# motorboard.net
KiCad netlist of a schematic drawn in EAGLE
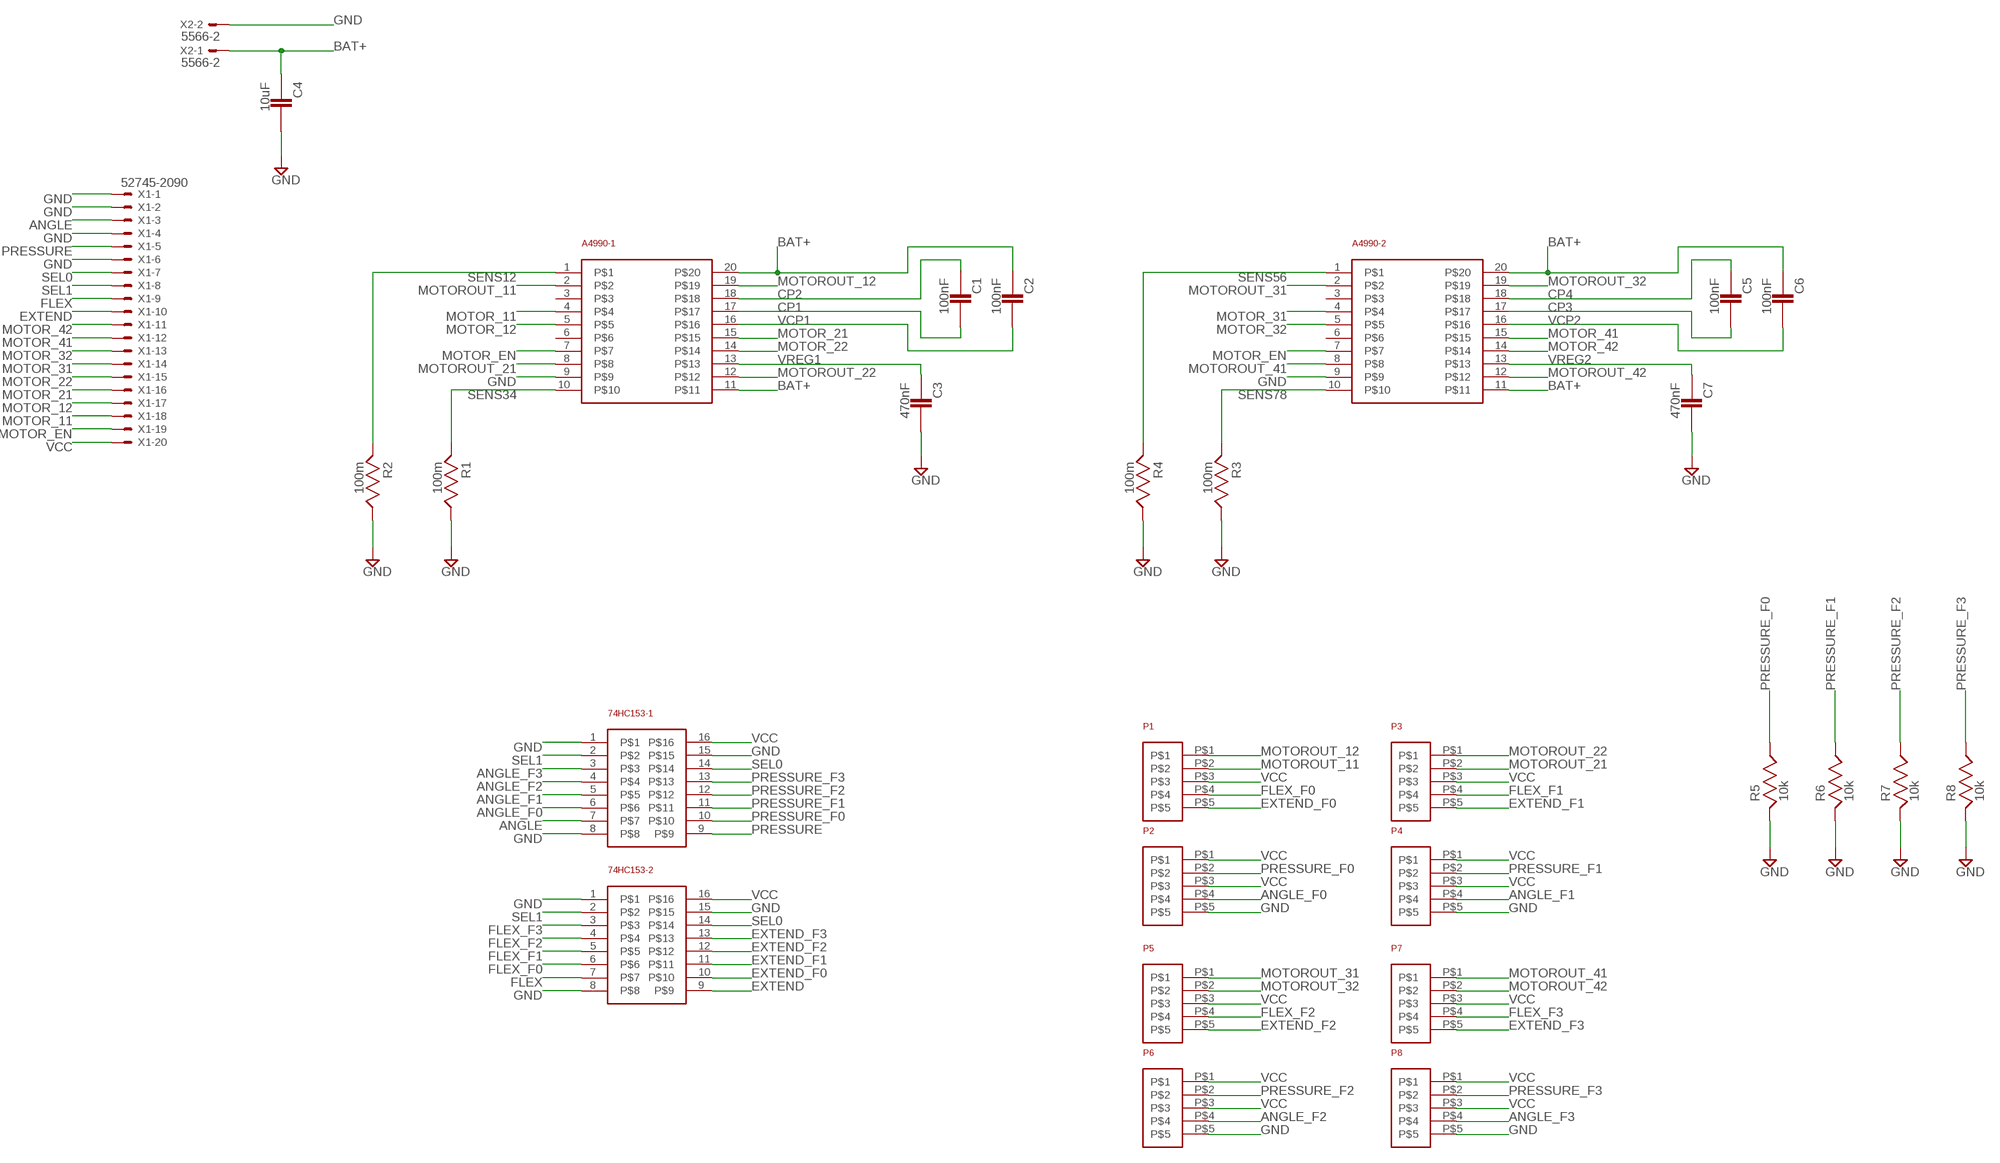
[diagram p0: schematic, sheet 1]

(export (version "E")
  (design (tool "Eeschema 10.0.6"))
  (components
    (comp (ref "74HC153-1")
      (value "74HC153")
      (footprint "eagle-import:SO-16_S-M")
      (libsource (lib "eagle-import") (part "74HC153"))
    )
    (comp (ref "74HC153-2")
      (value "74HC153")
      (footprint "eagle-import:SO-16_S-M")
      (libsource (lib "eagle-import") (part "74HC153"))
    )
    (comp (ref "A4990-1")
      (value "A4990")
      (footprint "eagle-import:A4990")
      (libsource (lib "eagle-import") (part "A4990"))
    )
    (comp (ref "A4990-2")
      (value "A4990")
      (footprint "eagle-import:A4990")
      (libsource (lib "eagle-import") (part "A4990"))
    )
    (comp (ref "C1")
      (value "100nF")
      (footprint "eagle-import:CC0603KRX7R9BB104_CAPC1608X90")
      (fields (field (name "MANUFACTURER") "YAGEO"))
      (libsource (lib "eagle-import") (part "CC0603KRX7R9BB104"))
    )
    (comp (ref "C2")
      (value "100nF")
      (footprint "eagle-import:CC0603KRX7R9BB104_CAPC1608X90")
      (fields (field (name "MANUFACTURER") "YAGEO"))
      (libsource (lib "eagle-import") (part "CC0603KRX7R9BB104"))
    )
    (comp (ref "C3")
      (value "470nF")
      (footprint "eagle-import:CC0603KRX7R9BB104_CAPC1608X90")
      (fields (field (name "MANUFACTURER") "YAGEO"))
      (libsource (lib "eagle-import") (part "CC0603KRX7R9BB104"))
    )
    (comp (ref "C4")
      (value "10uF")
      (footprint "eagle-import:CC0603KRX7R9BB104_CAPC1608X90")
      (fields (field (name "MANUFACTURER") "YAGEO"))
      (libsource (lib "eagle-import") (part "CC0603KRX7R9BB104"))
    )
    (comp (ref "C5")
      (value "100nF")
      (footprint "eagle-import:CC0603KRX7R9BB104_CAPC1608X90")
      (fields (field (name "MANUFACTURER") "YAGEO"))
      (libsource (lib "eagle-import") (part "CC0603KRX7R9BB104"))
    )
    (comp (ref "C6")
      (value "100nF")
      (footprint "eagle-import:CC0603KRX7R9BB104_CAPC1608X90")
      (fields (field (name "MANUFACTURER") "YAGEO"))
      (libsource (lib "eagle-import") (part "CC0603KRX7R9BB104"))
    )
    (comp (ref "C7")
      (value "470nF")
      (footprint "eagle-import:CC0603KRX7R9BB104_CAPC1608X90")
      (fields (field (name "MANUFACTURER") "YAGEO"))
      (libsource (lib "eagle-import") (part "CC0603KRX7R9BB104"))
    )
    (comp (ref "P1")
      (value "S5B-PH-SM4-TB")
      (footprint "eagle-import:S5B-PH-SM4-TB")
      (libsource (lib "eagle-import") (part "S5B-PH-SM4-TB"))
    )
    (comp (ref "P2")
      (value "S5B-PH-SM4-TB")
      (footprint "eagle-import:S5B-PH-SM4-TB")
      (libsource (lib "eagle-import") (part "S5B-PH-SM4-TB"))
    )
    (comp (ref "P3")
      (value "S5B-PH-SM4-TB")
      (footprint "eagle-import:S5B-PH-SM4-TB")
      (libsource (lib "eagle-import") (part "S5B-PH-SM4-TB"))
    )
    (comp (ref "P4")
      (value "S5B-PH-SM4-TB")
      (footprint "eagle-import:S5B-PH-SM4-TB")
      (libsource (lib "eagle-import") (part "S5B-PH-SM4-TB"))
    )
    (comp (ref "P5")
      (value "S5B-PH-SM4-TB")
      (footprint "eagle-import:S5B-PH-SM4-TB")
      (libsource (lib "eagle-import") (part "S5B-PH-SM4-TB"))
    )
    (comp (ref "P6")
      (value "S5B-PH-SM4-TB")
      (footprint "eagle-import:S5B-PH-SM4-TB")
      (libsource (lib "eagle-import") (part "S5B-PH-SM4-TB"))
    )
    (comp (ref "P7")
      (value "S5B-PH-SM4-TB")
      (footprint "eagle-import:S5B-PH-SM4-TB")
      (libsource (lib "eagle-import") (part "S5B-PH-SM4-TB"))
    )
    (comp (ref "P8")
      (value "S5B-PH-SM4-TB")
      (footprint "eagle-import:S5B-PH-SM4-TB")
      (libsource (lib "eagle-import") (part "S5B-PH-SM4-TB"))
    )
    (comp (ref "R1")
      (value "100m")
      (footprint "eagle-import:CRCW06031K00FKEA_RESC1608X55")
      (fields (field (name "MANUFACTURER") "VISHAY"))
      (libsource (lib "eagle-import") (part "CRCW06031K00FKEA"))
    )
    (comp (ref "R2")
      (value "100m")
      (footprint "eagle-import:CRCW06031K00FKEA_RESC1608X55")
      (fields (field (name "MANUFACTURER") "VISHAY"))
      (libsource (lib "eagle-import") (part "CRCW06031K00FKEA"))
    )
    (comp (ref "R3")
      (value "100m")
      (footprint "eagle-import:CRCW06031K00FKEA_RESC1608X55")
      (fields (field (name "MANUFACTURER") "VISHAY"))
      (libsource (lib "eagle-import") (part "CRCW06031K00FKEA"))
    )
    (comp (ref "R4")
      (value "100m")
      (footprint "eagle-import:CRCW06031K00FKEA_RESC1608X55")
      (fields (field (name "MANUFACTURER") "VISHAY"))
      (libsource (lib "eagle-import") (part "CRCW06031K00FKEA"))
    )
    (comp (ref "R5")
      (value "10k")
      (footprint "eagle-import:CRCW06031K00FKEA_RESC1608X55")
      (fields (field (name "MANUFACTURER") "VISHAY"))
      (libsource (lib "eagle-import") (part "CRCW06031K00FKEA"))
    )
    (comp (ref "R6")
      (value "10k")
      (footprint "eagle-import:CRCW06031K00FKEA_RESC1608X55")
      (fields (field (name "MANUFACTURER") "VISHAY"))
      (libsource (lib "eagle-import") (part "CRCW06031K00FKEA"))
    )
    (comp (ref "R7")
      (value "10k")
      (footprint "eagle-import:CRCW06031K00FKEA_RESC1608X55")
      (fields (field (name "MANUFACTURER") "VISHAY"))
      (libsource (lib "eagle-import") (part "CRCW06031K00FKEA"))
    )
    (comp (ref "R8")
      (value "10k")
      (footprint "eagle-import:CRCW06031K00FKEA_RESC1608X55")
      (fields (field (name "MANUFACTURER") "VISHAY"))
      (libsource (lib "eagle-import") (part "CRCW06031K00FKEA"))
    )
    (comp (ref "X1")
      (value "52745-2090")
      (footprint "eagle-import:52745-2090")
      (fields (field (name "MF") "WALDOM/MOLEX"))
      (libsource (lib "eagle-import") (part "52745-2090"))
    )
    (comp (ref "X2")
      (value "5566-2")
      (footprint "eagle-import:5566-2")
      (libsource (lib "eagle-import") (part "5566-2"))
    )
  )
  (nets
    (net (code "1") (name "/ANGLE") (class "Default")
      (node (ref "74HC153-1") (pin "7") (pinfunction "P$7_7") (pintype "bidirectional"))
      (node (ref "X1") (pin "3") (pinfunction "S_3") (pintype "passive"))
    )
    (net (code "2") (name "/ANGLE_F0") (class "Default")
      (node (ref "74HC153-1") (pin "6") (pinfunction "P$6_6") (pintype "bidirectional"))
      (node (ref "P2") (pin "P$4") (pinfunction "P$4_P$4") (pintype "bidirectional"))
    )
    (net (code "3") (name "/ANGLE_F1") (class "Default")
      (node (ref "74HC153-1") (pin "5") (pinfunction "P$5_5") (pintype "bidirectional"))
      (node (ref "P4") (pin "P$4") (pinfunction "P$4_P$4") (pintype "bidirectional"))
    )
    (net (code "4") (name "/ANGLE_F2") (class "Default")
      (node (ref "74HC153-1") (pin "4") (pinfunction "P$4_4") (pintype "bidirectional"))
      (node (ref "P6") (pin "P$4") (pinfunction "P$4_P$4") (pintype "bidirectional"))
    )
    (net (code "5") (name "/ANGLE_F3") (class "Default")
      (node (ref "74HC153-1") (pin "3") (pinfunction "P$3_3") (pintype "bidirectional"))
      (node (ref "P8") (pin "P$4") (pinfunction "P$4_P$4") (pintype "bidirectional"))
    )
    (net (code "6") (name "/BAT+") (class "Default")
      (node (ref "A4990-1") (pin "11") (pinfunction "P$11_11") (pintype "bidirectional"))
      (node (ref "A4990-1") (pin "20") (pinfunction "P$20_20") (pintype "bidirectional"))
      (node (ref "A4990-2") (pin "11") (pinfunction "P$11_11") (pintype "bidirectional"))
      (node (ref "A4990-2") (pin "20") (pinfunction "P$20_20") (pintype "bidirectional"))
      (node (ref "C2") (pin "1") (pinfunction "1_1") (pintype "passive"))
      (node (ref "C4") (pin "1") (pinfunction "1_1") (pintype "passive"))
      (node (ref "C6") (pin "1") (pinfunction "1_1") (pintype "passive"))
      (node (ref "X2") (pin "1") (pinfunction "S_1") (pintype "passive"))
    )
    (net (code "7") (name "/CP1") (class "Default")
      (node (ref "A4990-1") (pin "17") (pinfunction "P$17_17") (pintype "bidirectional"))
      (node (ref "C1") (pin "2") (pinfunction "2_2") (pintype "passive"))
    )
    (net (code "8") (name "/CP2") (class "Default")
      (node (ref "A4990-1") (pin "18") (pinfunction "P$18_18") (pintype "bidirectional"))
      (node (ref "C1") (pin "1") (pinfunction "1_1") (pintype "passive"))
    )
    (net (code "9") (name "/CP3") (class "Default")
      (node (ref "A4990-2") (pin "17") (pinfunction "P$17_17") (pintype "bidirectional"))
      (node (ref "C5") (pin "2") (pinfunction "2_2") (pintype "passive"))
    )
    (net (code "10") (name "/CP4") (class "Default")
      (node (ref "A4990-2") (pin "18") (pinfunction "P$18_18") (pintype "bidirectional"))
      (node (ref "C5") (pin "1") (pinfunction "1_1") (pintype "passive"))
    )
    (net (code "11") (name "/EXTEND") (class "Default")
      (node (ref "74HC153-2") (pin "9") (pinfunction "P$9_9") (pintype "bidirectional"))
      (node (ref "X1") (pin "10") (pinfunction "S_10") (pintype "passive"))
    )
    (net (code "12") (name "/EXTEND_F0") (class "Default")
      (node (ref "74HC153-2") (pin "10") (pinfunction "P$10_10") (pintype "bidirectional"))
      (node (ref "P1") (pin "P$5") (pinfunction "P$5_P$5") (pintype "bidirectional"))
    )
    (net (code "13") (name "/EXTEND_F1") (class "Default")
      (node (ref "74HC153-2") (pin "11") (pinfunction "P$11_11") (pintype "bidirectional"))
      (node (ref "P3") (pin "P$5") (pinfunction "P$5_P$5") (pintype "bidirectional"))
    )
    (net (code "14") (name "/EXTEND_F2") (class "Default")
      (node (ref "74HC153-2") (pin "12") (pinfunction "P$12_12") (pintype "bidirectional"))
      (node (ref "P5") (pin "P$5") (pinfunction "P$5_P$5") (pintype "bidirectional"))
    )
    (net (code "15") (name "/EXTEND_F3") (class "Default")
      (node (ref "74HC153-2") (pin "13") (pinfunction "P$13_13") (pintype "bidirectional"))
      (node (ref "P7") (pin "P$5") (pinfunction "P$5_P$5") (pintype "bidirectional"))
    )
    (net (code "16") (name "/FLEX") (class "Default")
      (node (ref "74HC153-2") (pin "7") (pinfunction "P$7_7") (pintype "bidirectional"))
      (node (ref "X1") (pin "9") (pinfunction "S_9") (pintype "passive"))
    )
    (net (code "17") (name "/FLEX_F0") (class "Default")
      (node (ref "74HC153-2") (pin "6") (pinfunction "P$6_6") (pintype "bidirectional"))
      (node (ref "P1") (pin "P$4") (pinfunction "P$4_P$4") (pintype "bidirectional"))
    )
    (net (code "18") (name "/FLEX_F1") (class "Default")
      (node (ref "74HC153-2") (pin "5") (pinfunction "P$5_5") (pintype "bidirectional"))
      (node (ref "P3") (pin "P$4") (pinfunction "P$4_P$4") (pintype "bidirectional"))
    )
    (net (code "19") (name "/FLEX_F2") (class "Default")
      (node (ref "74HC153-2") (pin "4") (pinfunction "P$4_4") (pintype "bidirectional"))
      (node (ref "P5") (pin "P$4") (pinfunction "P$4_P$4") (pintype "bidirectional"))
    )
    (net (code "20") (name "/FLEX_F3") (class "Default")
      (node (ref "74HC153-2") (pin "3") (pinfunction "P$3_3") (pintype "bidirectional"))
      (node (ref "P7") (pin "P$4") (pinfunction "P$4_P$4") (pintype "bidirectional"))
    )
    (net (code "21") (name "/MOTOROUT_11") (class "Default")
      (node (ref "A4990-1") (pin "2") (pinfunction "P$2_2") (pintype "bidirectional"))
      (node (ref "P1") (pin "P$2") (pinfunction "P$2_P$2") (pintype "bidirectional"))
    )
    (net (code "22") (name "/MOTOROUT_12") (class "Default")
      (node (ref "A4990-1") (pin "19") (pinfunction "P$19_19") (pintype "bidirectional"))
      (node (ref "P1") (pin "P$1") (pinfunction "P$1_P$1") (pintype "bidirectional"))
    )
    (net (code "23") (name "/MOTOROUT_21") (class "Default")
      (node (ref "A4990-1") (pin "8") (pinfunction "P$8_8") (pintype "bidirectional"))
      (node (ref "P3") (pin "P$2") (pinfunction "P$2_P$2") (pintype "bidirectional"))
    )
    (net (code "24") (name "/MOTOROUT_22") (class "Default")
      (node (ref "A4990-1") (pin "12") (pinfunction "P$12_12") (pintype "bidirectional"))
      (node (ref "P3") (pin "P$1") (pinfunction "P$1_P$1") (pintype "bidirectional"))
    )
    (net (code "25") (name "/MOTOROUT_31") (class "Default")
      (node (ref "A4990-2") (pin "2") (pinfunction "P$2_2") (pintype "bidirectional"))
      (node (ref "P5") (pin "P$1") (pinfunction "P$1_P$1") (pintype "bidirectional"))
    )
    (net (code "26") (name "/MOTOROUT_32") (class "Default")
      (node (ref "A4990-2") (pin "19") (pinfunction "P$19_19") (pintype "bidirectional"))
      (node (ref "P5") (pin "P$2") (pinfunction "P$2_P$2") (pintype "bidirectional"))
    )
    (net (code "27") (name "/MOTOROUT_41") (class "Default")
      (node (ref "A4990-2") (pin "8") (pinfunction "P$8_8") (pintype "bidirectional"))
      (node (ref "P7") (pin "P$1") (pinfunction "P$1_P$1") (pintype "bidirectional"))
    )
    (net (code "28") (name "/MOTOROUT_42") (class "Default")
      (node (ref "A4990-2") (pin "12") (pinfunction "P$12_12") (pintype "bidirectional"))
      (node (ref "P7") (pin "P$2") (pinfunction "P$2_P$2") (pintype "bidirectional"))
    )
    (net (code "29") (name "/MOTOR_11") (class "Default")
      (node (ref "A4990-1") (pin "4") (pinfunction "P$4_4") (pintype "bidirectional"))
      (node (ref "X1") (pin "18") (pinfunction "S_18") (pintype "passive"))
    )
    (net (code "30") (name "/MOTOR_12") (class "Default")
      (node (ref "A4990-1") (pin "5") (pinfunction "P$5_5") (pintype "bidirectional"))
      (node (ref "X1") (pin "17") (pinfunction "S_17") (pintype "passive"))
    )
    (net (code "31") (name "/MOTOR_21") (class "Default")
      (node (ref "A4990-1") (pin "15") (pinfunction "P$15_15") (pintype "bidirectional"))
      (node (ref "X1") (pin "16") (pinfunction "S_16") (pintype "passive"))
    )
    (net (code "32") (name "/MOTOR_22") (class "Default")
      (node (ref "A4990-1") (pin "14") (pinfunction "P$14_14") (pintype "bidirectional"))
      (node (ref "X1") (pin "15") (pinfunction "S_15") (pintype "passive"))
    )
    (net (code "33") (name "/MOTOR_31") (class "Default")
      (node (ref "A4990-2") (pin "4") (pinfunction "P$4_4") (pintype "bidirectional"))
      (node (ref "X1") (pin "14") (pinfunction "S_14") (pintype "passive"))
    )
    (net (code "34") (name "/MOTOR_32") (class "Default")
      (node (ref "A4990-2") (pin "5") (pinfunction "P$5_5") (pintype "bidirectional"))
      (node (ref "X1") (pin "13") (pinfunction "S_13") (pintype "passive"))
    )
    (net (code "35") (name "/MOTOR_41") (class "Default")
      (node (ref "A4990-2") (pin "15") (pinfunction "P$15_15") (pintype "bidirectional"))
      (node (ref "X1") (pin "12") (pinfunction "S_12") (pintype "passive"))
    )
    (net (code "36") (name "/MOTOR_42") (class "Default")
      (node (ref "A4990-2") (pin "14") (pinfunction "P$14_14") (pintype "bidirectional"))
      (node (ref "X1") (pin "11") (pinfunction "S_11") (pintype "passive"))
    )
    (net (code "37") (name "/MOTOR_EN") (class "Default")
      (node (ref "A4990-1") (pin "7") (pinfunction "P$7_7") (pintype "bidirectional"))
      (node (ref "A4990-2") (pin "7") (pinfunction "P$7_7") (pintype "bidirectional"))
      (node (ref "X1") (pin "19") (pinfunction "S_19") (pintype "passive"))
    )
    (net (code "38") (name "/PRESSURE") (class "Default")
      (node (ref "74HC153-1") (pin "9") (pinfunction "P$9_9") (pintype "bidirectional"))
      (node (ref "X1") (pin "5") (pinfunction "S_5") (pintype "passive"))
    )
    (net (code "39") (name "/PRESSURE_F0") (class "Default")
      (node (ref "74HC153-1") (pin "10") (pinfunction "P$10_10") (pintype "bidirectional"))
      (node (ref "P2") (pin "P$2") (pinfunction "P$2_P$2") (pintype "bidirectional"))
      (node (ref "R5") (pin "2") (pinfunction "2_2") (pintype "passive"))
    )
    (net (code "40") (name "/PRESSURE_F1") (class "Default")
      (node (ref "74HC153-1") (pin "11") (pinfunction "P$11_11") (pintype "bidirectional"))
      (node (ref "P4") (pin "P$2") (pinfunction "P$2_P$2") (pintype "bidirectional"))
      (node (ref "R6") (pin "2") (pinfunction "2_2") (pintype "passive"))
    )
    (net (code "41") (name "/PRESSURE_F2") (class "Default")
      (node (ref "74HC153-1") (pin "12") (pinfunction "P$12_12") (pintype "bidirectional"))
      (node (ref "P6") (pin "P$2") (pinfunction "P$2_P$2") (pintype "bidirectional"))
      (node (ref "R7") (pin "2") (pinfunction "2_2") (pintype "passive"))
    )
    (net (code "42") (name "/PRESSURE_F3") (class "Default")
      (node (ref "74HC153-1") (pin "13") (pinfunction "P$13_13") (pintype "bidirectional"))
      (node (ref "P8") (pin "P$2") (pinfunction "P$2_P$2") (pintype "bidirectional"))
      (node (ref "R8") (pin "2") (pinfunction "2_2") (pintype "passive"))
    )
    (net (code "43") (name "/SEL0") (class "Default")
      (node (ref "74HC153-1") (pin "14") (pinfunction "P$14_14") (pintype "bidirectional"))
      (node (ref "74HC153-2") (pin "14") (pinfunction "P$14_14") (pintype "bidirectional"))
      (node (ref "X1") (pin "7") (pinfunction "S_7") (pintype "passive"))
    )
    (net (code "44") (name "/SEL1") (class "Default")
      (node (ref "74HC153-1") (pin "2") (pinfunction "P$2_2") (pintype "bidirectional"))
      (node (ref "74HC153-2") (pin "2") (pinfunction "P$2_2") (pintype "bidirectional"))
      (node (ref "X1") (pin "8") (pinfunction "S_8") (pintype "passive"))
    )
    (net (code "45") (name "/SENS12") (class "Default")
      (node (ref "A4990-1") (pin "1") (pinfunction "P$1_1") (pintype "bidirectional"))
      (node (ref "R2") (pin "1") (pinfunction "1_1") (pintype "passive"))
    )
    (net (code "46") (name "/SENS34") (class "Default")
      (node (ref "A4990-1") (pin "10") (pinfunction "P$10_10") (pintype "bidirectional"))
      (node (ref "R1") (pin "1") (pinfunction "1_1") (pintype "passive"))
    )
    (net (code "47") (name "/SENS56") (class "Default")
      (node (ref "A4990-2") (pin "1") (pinfunction "P$1_1") (pintype "bidirectional"))
      (node (ref "R4") (pin "1") (pinfunction "1_1") (pintype "passive"))
    )
    (net (code "48") (name "/SENS78") (class "Default")
      (node (ref "A4990-2") (pin "10") (pinfunction "P$10_10") (pintype "bidirectional"))
      (node (ref "R3") (pin "1") (pinfunction "1_1") (pintype "passive"))
    )
    (net (code "49") (name "/VCC") (class "Default")
      (node (ref "74HC153-1") (pin "16") (pinfunction "P$16_16") (pintype "bidirectional"))
      (node (ref "74HC153-2") (pin "16") (pinfunction "P$16_16") (pintype "bidirectional"))
      (node (ref "P1") (pin "P$3") (pinfunction "P$3_P$3") (pintype "bidirectional"))
      (node (ref "P2") (pin "P$1") (pinfunction "P$1_P$1") (pintype "bidirectional"))
      (node (ref "P2") (pin "P$3") (pinfunction "P$3_P$3") (pintype "bidirectional"))
      (node (ref "P3") (pin "P$3") (pinfunction "P$3_P$3") (pintype "bidirectional"))
      (node (ref "P4") (pin "P$1") (pinfunction "P$1_P$1") (pintype "bidirectional"))
      (node (ref "P4") (pin "P$3") (pinfunction "P$3_P$3") (pintype "bidirectional"))
      (node (ref "P5") (pin "P$3") (pinfunction "P$3_P$3") (pintype "bidirectional"))
      (node (ref "P6") (pin "P$1") (pinfunction "P$1_P$1") (pintype "bidirectional"))
      (node (ref "P6") (pin "P$3") (pinfunction "P$3_P$3") (pintype "bidirectional"))
      (node (ref "P7") (pin "P$3") (pinfunction "P$3_P$3") (pintype "bidirectional"))
      (node (ref "P8") (pin "P$1") (pinfunction "P$1_P$1") (pintype "bidirectional"))
      (node (ref "P8") (pin "P$3") (pinfunction "P$3_P$3") (pintype "bidirectional"))
      (node (ref "X1") (pin "20") (pinfunction "S_20") (pintype "passive"))
    )
    (net (code "50") (name "/VCP1") (class "Default")
      (node (ref "A4990-1") (pin "16") (pinfunction "P$16_16") (pintype "bidirectional"))
      (node (ref "C2") (pin "2") (pinfunction "2_2") (pintype "passive"))
    )
    (net (code "51") (name "/VCP2") (class "Default")
      (node (ref "A4990-2") (pin "16") (pinfunction "P$16_16") (pintype "bidirectional"))
      (node (ref "C6") (pin "2") (pinfunction "2_2") (pintype "passive"))
    )
    (net (code "52") (name "/VREG1") (class "Default")
      (node (ref "A4990-1") (pin "13") (pinfunction "P$13_13") (pintype "bidirectional"))
      (node (ref "C3") (pin "1") (pinfunction "1_1") (pintype "passive"))
    )
    (net (code "53") (name "/VREG2") (class "Default")
      (node (ref "A4990-2") (pin "13") (pinfunction "P$13_13") (pintype "bidirectional"))
      (node (ref "C7") (pin "1") (pinfunction "1_1") (pintype "passive"))
    )
    (net (code "54") (name "GND") (class "Default")
      (node (ref "74HC153-1") (pin "1") (pinfunction "P$1_1") (pintype "bidirectional"))
      (node (ref "74HC153-1") (pin "15") (pinfunction "P$15_15") (pintype "bidirectional"))
      (node (ref "74HC153-1") (pin "8") (pinfunction "P$8_8") (pintype "bidirectional"))
      (node (ref "74HC153-2") (pin "1") (pinfunction "P$1_1") (pintype "bidirectional"))
      (node (ref "74HC153-2") (pin "15") (pinfunction "P$15_15") (pintype "bidirectional"))
      (node (ref "74HC153-2") (pin "8") (pinfunction "P$8_8") (pintype "bidirectional"))
      (node (ref "A4990-1") (pin "9") (pinfunction "P$9_9") (pintype "bidirectional"))
      (node (ref "A4990-2") (pin "9") (pinfunction "P$9_9") (pintype "bidirectional"))
      (node (ref "C3") (pin "2") (pinfunction "2_2") (pintype "passive"))
      (node (ref "C4") (pin "2") (pinfunction "2_2") (pintype "passive"))
      (node (ref "C7") (pin "2") (pinfunction "2_2") (pintype "passive"))
      (node (ref "P2") (pin "P$5") (pinfunction "P$5_P$5") (pintype "bidirectional"))
      (node (ref "P4") (pin "P$5") (pinfunction "P$5_P$5") (pintype "bidirectional"))
      (node (ref "P6") (pin "P$5") (pinfunction "P$5_P$5") (pintype "bidirectional"))
      (node (ref "P8") (pin "P$5") (pinfunction "P$5_P$5") (pintype "bidirectional"))
      (node (ref "R1") (pin "2") (pinfunction "2_2") (pintype "passive"))
      (node (ref "R2") (pin "2") (pinfunction "2_2") (pintype "passive"))
      (node (ref "R3") (pin "2") (pinfunction "2_2") (pintype "passive"))
      (node (ref "R4") (pin "2") (pinfunction "2_2") (pintype "passive"))
      (node (ref "R5") (pin "1") (pinfunction "1_1") (pintype "passive"))
      (node (ref "R6") (pin "1") (pinfunction "1_1") (pintype "passive"))
      (node (ref "R7") (pin "1") (pinfunction "1_1") (pintype "passive"))
      (node (ref "R8") (pin "1") (pinfunction "1_1") (pintype "passive"))
      (node (ref "X1") (pin "1") (pinfunction "S_1") (pintype "passive"))
      (node (ref "X1") (pin "2") (pinfunction "S_2") (pintype "passive"))
      (node (ref "X1") (pin "4") (pinfunction "S_4") (pintype "passive"))
      (node (ref "X1") (pin "6") (pinfunction "S_6") (pintype "passive"))
      (node (ref "X2") (pin "2") (pinfunction "S_2") (pintype "passive"))
    )
    (net (code "55") (name "unconnected-(A4990-1-P$3-Pad3)") (class "Default")
      (node (ref "A4990-1") (pin "3") (pinfunction "P$3_3") (pintype "bidirectional"))
    )
    (net (code "56") (name "unconnected-(A4990-1-P$6-Pad6)") (class "Default")
      (node (ref "A4990-1") (pin "6") (pinfunction "P$6_6") (pintype "bidirectional"))
    )
    (net (code "57") (name "unconnected-(A4990-2-P$3-Pad3)") (class "Default")
      (node (ref "A4990-2") (pin "3") (pinfunction "P$3_3") (pintype "bidirectional"))
    )
    (net (code "58") (name "unconnected-(A4990-2-P$6-Pad6)") (class "Default")
      (node (ref "A4990-2") (pin "6") (pinfunction "P$6_6") (pintype "bidirectional"))
    )
  )
)
